# OPEnS-Power-7_2.net
KiCad netlist of a schematic drawn in EAGLE
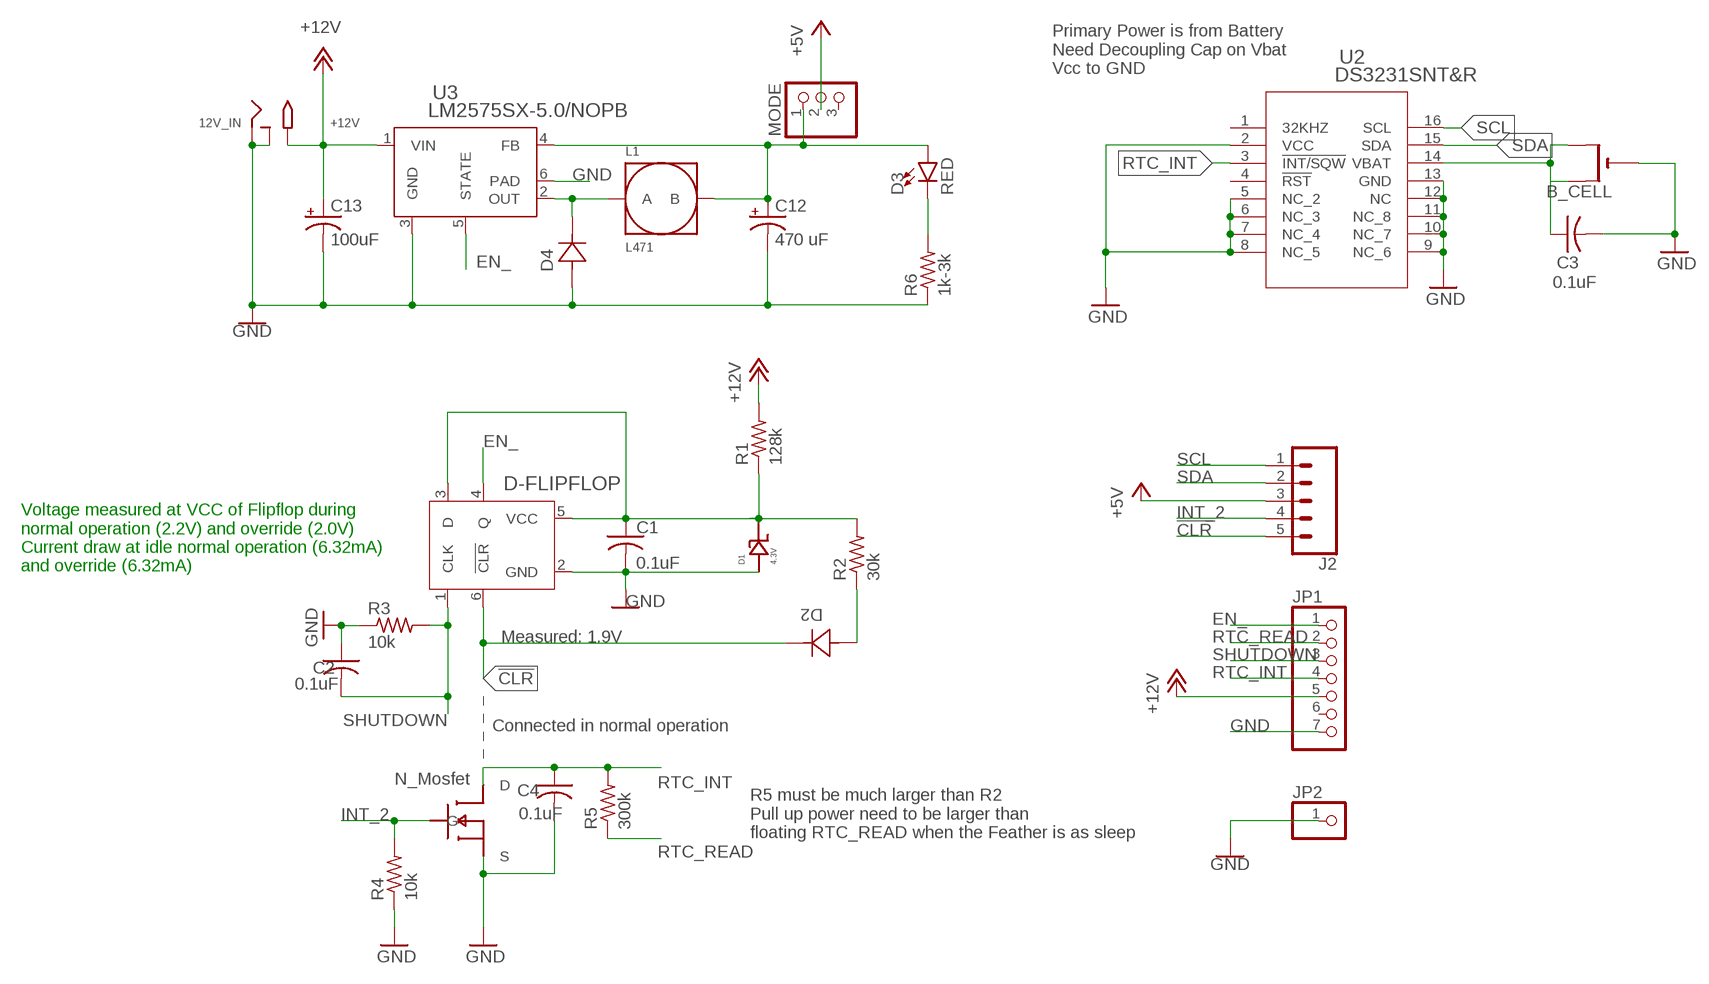
[diagram p0: schematic, sheet 1]

(export (version "E")
  (design (tool "Eeschema 10.0.6"))
  (components
    (comp (ref "12V_IN")
      (value "2.1MMJACKSMT")
      (footprint "eagle-import:DCJACK_2MM_SMT")
      (libsource (lib "eagle-import") (part "2.1MMJACKSMT"))
    )
    (comp (ref "B_CELL")
      (value "CR1220SMT")
      (footprint "eagle-import:CR1220-SMD")
      (libsource (lib "eagle-import") (part "CR1220SMT"))
    )
    (comp (ref "C1")
      (value "0.1uF")
      (footprint "eagle-import:C1206")
      (libsource (lib "eagle-import") (part "C-USC1206"))
    )
    (comp (ref "C2")
      (value "0.1uF")
      (footprint "eagle-import:C1206")
      (libsource (lib "eagle-import") (part "C-USC1206"))
    )
    (comp (ref "C3")
      (value "0.1uF")
      (footprint "eagle-import:C1206")
      (libsource (lib "eagle-import") (part "C-USC1206"))
    )
    (comp (ref "C4")
      (value "0.1uF")
      (footprint "eagle-import:C1206")
      (libsource (lib "eagle-import") (part "C-USC1206"))
    )
    (comp (ref "C12")
      (value "470 uF")
      (footprint "eagle-import:153CLV-0810")
      (libsource (lib "eagle-import") (part "rcl_334_CPOL-US153CLV-0810"))
    )
    (comp (ref "C13")
      (value "100uF")
      (footprint "eagle-import:153CLV-0505")
      (libsource (lib "eagle-import") (part "CPOL-US153CLV-0505"))
    )
    (comp (ref "D-FLIPFLOP")
      (value "SN74LVC1G175DBVR")
      (footprint "eagle-import:DBV6")
      (libsource (lib "eagle-import") (part "SN74LVC1G175DBVR"))
    )
    (comp (ref "D1")
      (value "4.3V")
      (footprint "eagle-import:DO-219AC")
      (libsource (lib "eagle-import") (part "ZENER-DO219"))
    )
    (comp (ref "D2")
      (value "S1A-13-F")
      (footprint "eagle-import:SMA")
      (fields (field (name "MANUFACTURER_PART_NUMBER") "S1A13F"))
      (libsource (lib "eagle-import") (part "S1A-13-F"))
    )
    (comp (ref "D3")
      (value "RED")
      (footprint "eagle-import:LED-1206")
      (libsource (lib "eagle-import") (part "LED-RED1206"))
    )
    (comp (ref "D4")
      (value "S1A-13-F")
      (footprint "eagle-import:SMA")
      (fields (field (name "MANUFACTURER_PART_NUMBER") "S1A13F"))
      (libsource (lib "eagle-import") (part "S1A-13-F"))
    )
    (comp (ref "J2")
      (value "CONN_05")
      (footprint "eagle-import:1X05")
      (libsource (lib "eagle-import") (part "CONN_05"))
    )
    (comp (ref "JP1")
      (value "PINHD-1X7")
      (footprint "eagle-import:1X07")
      (libsource (lib "eagle-import") (part "PINHD-1X7"))
    )
    (comp (ref "JP2")
      (value "PINHD-1X1")
      (footprint "eagle-import:1X01")
      (libsource (lib "eagle-import") (part "PINHD-1X1"))
    )
    (comp (ref "L1")
      (value "L471")
      (footprint "eagle-import:12-12")
      (libsource (lib "eagle-import") (part "L471"))
    )
    (comp (ref "MODE")
      (value "PINHD-1X3")
      (footprint "eagle-import:1X03")
      (libsource (lib "eagle-import") (part "PINHD-1X3"))
    )
    (comp (ref "MOSFET")
      (value "MOSFET-SOT23F")
      (footprint "eagle-import:SOT-23F")
      (libsource (lib "eagle-import") (part "MOSFET-SOT23F"))
    )
    (comp (ref "R1")
      (value "128k")
      (footprint "eagle-import:R1206")
      (libsource (lib "eagle-import") (part "R-US_R1206"))
    )
    (comp (ref "R2")
      (value "30k")
      (footprint "eagle-import:R1206")
      (libsource (lib "eagle-import") (part "R-US_R1206"))
    )
    (comp (ref "R3")
      (value "10k")
      (footprint "eagle-import:R1206")
      (libsource (lib "eagle-import") (part "R-US_R1206"))
    )
    (comp (ref "R4")
      (value "10k")
      (footprint "eagle-import:R1206")
      (libsource (lib "eagle-import") (part "R-US_R1206"))
    )
    (comp (ref "R5")
      (value "300k")
      (footprint "eagle-import:R1206")
      (libsource (lib "eagle-import") (part "R-US_R1206"))
    )
    (comp (ref "R6")
      (value "1k-3k")
      (footprint "eagle-import:R1206")
      (libsource (lib "eagle-import") (part "R-US_R1206"))
    )
    (comp (ref "U2")
      (value "DS3231SNT&R")
      (footprint "eagle-import:21-0042B_16")
      (fields (field (name "MANUFACTURER_PART_NUMBER") "DS3231SN#T&R"))
      (libsource (lib "eagle-import") (part "DS3231SNT&R"))
    )
    (comp (ref "U3")
      (value "LM2575SX-5.0/NOPB")
      (footprint "eagle-import:KTT0005B")
      (fields (field (name "MANUFACTURER_PART_NUMBER") "LM2575SX5.0NOPB"))
      (libsource (lib "eagle-import") (part "LM2575SX-5.0/NOPB"))
    )
  )
  (nets
    (net (code "1") (name "+5V") (class "Default")
      (node (ref "J2") (pin "3") (pinfunction "3_3") (pintype "passive"))
      (node (ref "MODE") (pin "2") (pinfunction "2_2") (pintype "passive"))
    )
    (net (code "2") (name "+12V") (class "Default")
      (node (ref "12V_IN") (pin "PWR2") (pinfunction "TIP_PWR2") (pintype "bidirectional"))
      (node (ref "C13") (pin "+") (pinfunction "+_+") (pintype "passive"))
      (node (ref "JP1") (pin "5") (pinfunction "5_5") (pintype "passive"))
      (node (ref "R1") (pin "2") (pinfunction "2_2") (pintype "passive"))
      (node (ref "U3") (pin "1") (pinfunction "VIN_1") (pintype "power_in"))
    )
    (net (code "3") (name "/EN_") (class "Default")
      (node (ref "D-FLIPFLOP") (pin "4") (pinfunction "Q_4") (pintype "output"))
      (node (ref "JP1") (pin "1") (pinfunction "1_1") (pintype "passive"))
      (node (ref "U3") (pin "5") (pinfunction "STATE_5") (pintype "input"))
    )
    (net (code "4") (name "/INT_2") (class "Default")
      (node (ref "J2") (pin "4") (pinfunction "4_4") (pintype "passive"))
      (node (ref "MOSFET") (pin "G") (pinfunction "G_G") (pintype "bidirectional"))
      (node (ref "R4") (pin "2") (pinfunction "2_2") (pintype "passive"))
    )
    (net (code "5") (name "/RTC_READ") (class "Default")
      (node (ref "JP1") (pin "2") (pinfunction "2_2") (pintype "passive"))
      (node (ref "R5") (pin "1") (pinfunction "1_1") (pintype "passive"))
    )
    (net (code "6") (name "/SHUTDOWN") (class "Default")
      (node (ref "C2") (pin "2") (pinfunction "2_2") (pintype "passive"))
      (node (ref "D-FLIPFLOP") (pin "1") (pinfunction "CLK_1") (pintype "input"))
      (node (ref "JP1") (pin "3") (pinfunction "3_3") (pintype "passive"))
      (node (ref "R3") (pin "2") (pinfunction "2_2") (pintype "passive"))
    )
    (net (code "7") (name "/~{CLR}") (class "Default")
      (node (ref "D-FLIPFLOP") (pin "6") (pinfunction "~{CLR}_6") (pintype "input"))
      (node (ref "D2") (pin "1") (pinfunction "1_1") (pintype "passive"))
      (node (ref "J2") (pin "5") (pinfunction "5_5") (pintype "passive"))
    )
    (net (code "8") (name "GND") (class "Default")
      (node (ref "12V_IN") (pin "GND") (pinfunction "RING_GND") (pintype "bidirectional"))
      (node (ref "12V_IN") (pin "GNDBREAK") (pinfunction "RING_SW_GNDBREAK") (pintype "bidirectional"))
      (node (ref "B_CELL") (pin "-") (pinfunction "-_-") (pintype "passive"))
      (node (ref "C1") (pin "2") (pinfunction "2_2") (pintype "passive"))
      (node (ref "C12") (pin "-") (pinfunction "-_-") (pintype "passive"))
      (node (ref "C13") (pin "-") (pinfunction "-_-") (pintype "passive"))
      (node (ref "C2") (pin "1") (pinfunction "1_1") (pintype "passive"))
      (node (ref "C3") (pin "2") (pinfunction "2_2") (pintype "passive"))
      (node (ref "C4") (pin "2") (pinfunction "2_2") (pintype "passive"))
      (node (ref "D-FLIPFLOP") (pin "2") (pinfunction "GND_2") (pintype "power_in"))
      (node (ref "D1") (pin "BCK") (pinfunction "BCK_BCK") (pintype "bidirectional"))
      (node (ref "D4") (pin "2") (pinfunction "2_2") (pintype "passive"))
      (node (ref "JP1") (pin "7") (pinfunction "7_7") (pintype "passive"))
      (node (ref "JP2") (pin "1") (pinfunction "1_1") (pintype "passive"))
      (node (ref "MOSFET") (pin "S") (pinfunction "S_S") (pintype "bidirectional"))
      (node (ref "R3") (pin "1") (pinfunction "1_1") (pintype "passive"))
      (node (ref "R4") (pin "1") (pinfunction "1_1") (pintype "passive"))
      (node (ref "R6") (pin "1") (pinfunction "1_1") (pintype "passive"))
      (node (ref "U2") (pin "10") (pinfunction "NC_7_10") (pintype "passive"))
      (node (ref "U2") (pin "11") (pinfunction "NC_8_11") (pintype "passive"))
      (node (ref "U2") (pin "12") (pinfunction "NC_12") (pintype "passive"))
      (node (ref "U2") (pin "13") (pinfunction "GND_13") (pintype "power_in"))
      (node (ref "U2") (pin "2") (pinfunction "VCC_2") (pintype "power_in"))
      (node (ref "U2") (pin "5") (pinfunction "NC_2_5") (pintype "passive"))
      (node (ref "U2") (pin "6") (pinfunction "NC_3_6") (pintype "passive"))
      (node (ref "U2") (pin "7") (pinfunction "NC_4_7") (pintype "passive"))
      (node (ref "U2") (pin "8") (pinfunction "NC_5_8") (pintype "passive"))
      (node (ref "U2") (pin "9") (pinfunction "NC_6_9") (pintype "passive"))
      (node (ref "U3") (pin "3") (pinfunction "GND_3") (pintype "power_in"))
      (node (ref "U3") (pin "6") (pinfunction "PAD_6") (pintype "passive"))
    )
    (net (code "9") (name "Net-(B_CELL-+)") (class "Default")
      (node (ref "B_CELL") (pin "+$1") (pinfunction "+_+$1") (pintype "passive"))
      (node (ref "B_CELL") (pin "+$2") (pinfunction "+1_+$2") (pintype "passive"))
      (node (ref "C3") (pin "1") (pinfunction "1_1") (pintype "passive"))
      (node (ref "U2") (pin "14") (pinfunction "VBAT_14") (pintype "power_in"))
    )
    (net (code "10") (name "Net-(D-FLIPFLOP-D)") (class "Default")
      (node (ref "C1") (pin "1") (pinfunction "1_1") (pintype "passive"))
      (node (ref "D-FLIPFLOP") (pin "3") (pinfunction "D_3") (pintype "input"))
      (node (ref "D-FLIPFLOP") (pin "5") (pinfunction "VCC_5") (pintype "power_in"))
      (node (ref "D1") (pin "FNT") (pinfunction "FNT_FNT") (pintype "bidirectional"))
      (node (ref "R1") (pin "1") (pinfunction "1_1") (pintype "passive"))
      (node (ref "R2") (pin "2") (pinfunction "2_2") (pintype "passive"))
    )
    (net (code "11") (name "Net-(D2-Pad2)") (class "Default")
      (node (ref "D2") (pin "2") (pinfunction "2_2") (pintype "passive"))
      (node (ref "R2") (pin "1") (pinfunction "1_1") (pintype "passive"))
    )
    (net (code "12") (name "Net-(D3-PadC)") (class "Default")
      (node (ref "D3") (pin "C") (pinfunction "C_C") (pintype "passive"))
      (node (ref "R6") (pin "2") (pinfunction "2_2") (pintype "passive"))
    )
    (net (code "13") (name "Net-(U3-FB)") (class "Default")
      (node (ref "C12") (pin "+") (pinfunction "+_+") (pintype "passive"))
      (node (ref "D3") (pin "A") (pinfunction "A_A") (pintype "passive"))
      (node (ref "L1") (pin "B") (pinfunction "B_B") (pintype "bidirectional"))
      (node (ref "MODE") (pin "1") (pinfunction "1_1") (pintype "passive"))
      (node (ref "U3") (pin "4") (pinfunction "FB_4") (pintype "input"))
    )
    (net (code "14") (name "Net-(U3-OUT)") (class "Default")
      (node (ref "D4") (pin "1") (pinfunction "1_1") (pintype "passive"))
      (node (ref "L1") (pin "A") (pinfunction "A_A") (pintype "bidirectional"))
      (node (ref "U3") (pin "2") (pinfunction "OUT_2") (pintype "output"))
    )
    (net (code "15") (name "RTC_INT") (class "Default")
      (node (ref "C4") (pin "1") (pinfunction "1_1") (pintype "passive"))
      (node (ref "JP1") (pin "4") (pinfunction "4_4") (pintype "passive"))
      (node (ref "MOSFET") (pin "D") (pinfunction "D_D") (pintype "bidirectional"))
      (node (ref "R5") (pin "2") (pinfunction "2_2") (pintype "passive"))
      (node (ref "U2") (pin "3") (pinfunction "~{INT/SQW}_3") (pintype "passive"))
    )
    (net (code "16") (name "SCL") (class "Default")
      (node (ref "J2") (pin "1") (pinfunction "1_1") (pintype "passive"))
      (node (ref "U2") (pin "16") (pinfunction "SCL_16") (pintype "passive"))
    )
    (net (code "17") (name "SDA") (class "Default")
      (node (ref "J2") (pin "2") (pinfunction "2_2") (pintype "passive"))
      (node (ref "U2") (pin "15") (pinfunction "SDA_15") (pintype "passive"))
    )
    (net (code "18") (name "unconnected-(JP1-Pad6)") (class "Default")
      (node (ref "JP1") (pin "6") (pinfunction "6_6") (pintype "passive"))
    )
    (net (code "19") (name "unconnected-(MODE-Pad3)") (class "Default")
      (node (ref "MODE") (pin "3") (pinfunction "3_3") (pintype "passive"))
    )
    (net (code "20") (name "unconnected-(U2-32KHZ-Pad1)") (class "Default")
      (node (ref "U2") (pin "1") (pinfunction "32KHZ_1") (pintype "passive"))
    )
    (net (code "21") (name "unconnected-(U2-~{RST}-Pad4)") (class "Default")
      (node (ref "U2") (pin "4") (pinfunction "~{RST}_4") (pintype "passive"))
    )
  )
)
